# schema.net
KiCad netlist of a schematic drawn in EAGLE
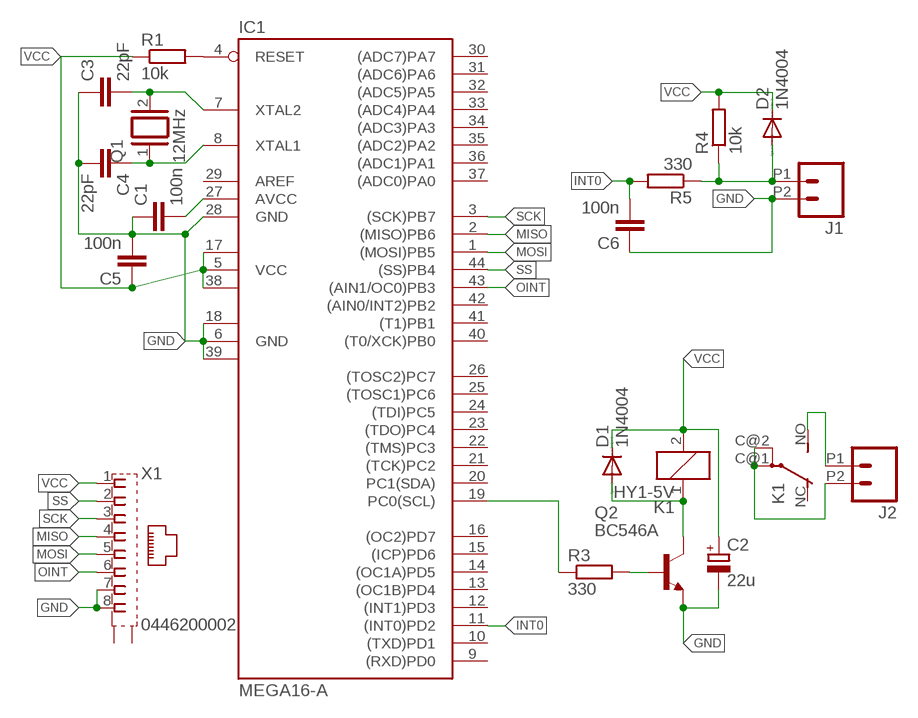
[diagram p0: schematic, sheet 1]

(export (version "E")
  (design (tool "Eeschema 10.0.6"))
  (components
    (comp (ref "C1")
      (value "100n")
      (footprint "eagle-import:C050-024X044")
      (libsource (lib "eagle-import") (part "C-EU050-024X044"))
    )
    (comp (ref "C2")
      (value "22u")
      (footprint "eagle-import:E2,5-6")
      (libsource (lib "eagle-import") (part "CPOL-EUE2.5-6"))
    )
    (comp (ref "C3")
      (value "22pF")
      (footprint "eagle-import:C050-024X044")
      (libsource (lib "eagle-import") (part "C-EU050-024X044"))
    )
    (comp (ref "C4")
      (value "22pF")
      (footprint "eagle-import:C050-024X044")
      (libsource (lib "eagle-import") (part "C-EU050-024X044"))
    )
    (comp (ref "C5")
      (value "100n")
      (footprint "eagle-import:C050-024X044")
      (libsource (lib "eagle-import") (part "C-EU050-024X044"))
    )
    (comp (ref "C6")
      (value "100n")
      (footprint "eagle-import:C050-024X044")
      (libsource (lib "eagle-import") (part "C-EU050-024X044"))
    )
    (comp (ref "D1")
      (value "1N4004")
      (footprint "eagle-import:DO41-10")
      (libsource (lib "eagle-import") (part "1N4004"))
    )
    (comp (ref "D2")
      (value "1N4004")
      (footprint "eagle-import:DO41-10")
      (libsource (lib "eagle-import") (part "1N4004"))
    )
    (comp (ref "IC1")
      (value "MEGA16-A")
      (footprint "eagle-import:TQFP44")
      (fields (field (name "MPN") "ATMEGA16-16AU"))
      (libsource (lib "eagle-import") (part "MEGA16-A"))
    )
    (comp (ref "J1")
      (value "M022.54MM_SCREWTERM")
      (footprint "eagle-import:1X02_2.54_SCREWTERM")
      (libsource (lib "eagle-import") (part "M022.54MM_SCREWTERM"))
    )
    (comp (ref "J2")
      (value "M022.54MM_SCREWTERM")
      (footprint "eagle-import:1X02_2.54_SCREWTERM")
      (libsource (lib "eagle-import") (part "M022.54MM_SCREWTERM"))
    )
    (comp (ref "K1")
      (value "HY1-5V")
      (footprint "eagle-import:HY")
      (fields (field (name "MF") "AROMAT/ MATSUSHITA"))
      (libsource (lib "eagle-import") (part "HY1-5V"))
    )
    (comp (ref "Q1")
      (value "12MHz")
      (footprint "eagle-import:QS")
      (libsource (lib "eagle-import") (part "XTAL/S"))
    )
    (comp (ref "Q2")
      (value "BC546A")
      (footprint "eagle-import:TO92-EBC")
      (libsource (lib "eagle-import") (part "BC546A"))
    )
    (comp (ref "R1")
      (value "10k")
      (footprint "eagle-import:0204_7")
      (libsource (lib "eagle-import") (part "R-EU_0204/7"))
    )
    (comp (ref "R3")
      (value "330")
      (footprint "eagle-import:0204_7")
      (libsource (lib "eagle-import") (part "R-EU_0204/7"))
    )
    (comp (ref "R4")
      (value "10k")
      (footprint "eagle-import:0204_7")
      (libsource (lib "eagle-import") (part "R-EU_0204/7"))
    )
    (comp (ref "R5")
      (value "330")
      (footprint "eagle-import:0204_7")
      (libsource (lib "eagle-import") (part "R-EU_0204/7"))
    )
    (comp (ref "X1")
      (value "0446200002")
      (footprint "eagle-import:0446200002")
      (fields (field (name "MF") "MOLEX"))
      (libsource (lib "eagle-import") (part "0446200002"))
    )
  )
  (nets
    (net (code "1") (name "GND") (class "Default")
      (node (ref "C1") (pin "1") (pinfunction "1_1") (pintype "passive"))
      (node (ref "C2") (pin "-") (pinfunction "-_-") (pintype "passive"))
      (node (ref "C3") (pin "1") (pinfunction "1_1") (pintype "passive"))
      (node (ref "C4") (pin "2") (pinfunction "2_2") (pintype "passive"))
      (node (ref "C5") (pin "2") (pinfunction "2_2") (pintype "passive"))
      (node (ref "C6") (pin "1") (pinfunction "1_1") (pintype "passive"))
      (node (ref "IC1") (pin "18") (pinfunction "GND1_18") (pintype "power_in"))
      (node (ref "IC1") (pin "28") (pinfunction "GND_28") (pintype "power_in"))
      (node (ref "IC1") (pin "39") (pinfunction "GND2_39") (pintype "power_in"))
      (node (ref "IC1") (pin "6") (pinfunction "GND_6") (pintype "power_in"))
      (node (ref "J1") (pin "P2") (pinfunction "2_P2") (pintype "passive"))
      (node (ref "Q2") (pin "E") (pinfunction "E_E") (pintype "passive"))
      (node (ref "X1") (pin "7") (pinfunction "7_7") (pintype "passive"))
      (node (ref "X1") (pin "8") (pinfunction "8_8") (pintype "passive"))
    )
    (net (code "2") (name "INT0") (class "Default")
      (node (ref "C6") (pin "2") (pinfunction "2_2") (pintype "passive"))
      (node (ref "IC1") (pin "11") (pinfunction "(INT0)PD2_11") (pintype "bidirectional"))
      (node (ref "R5") (pin "2") (pinfunction "2_2") (pintype "passive"))
    )
    (net (code "3") (name "MISO") (class "Default")
      (node (ref "IC1") (pin "2") (pinfunction "(MISO)PB6_2") (pintype "bidirectional"))
      (node (ref "X1") (pin "4") (pinfunction "4_4") (pintype "passive"))
    )
    (net (code "4") (name "MOSI") (class "Default")
      (node (ref "IC1") (pin "1") (pinfunction "(MOSI)PB5_1") (pintype "bidirectional"))
      (node (ref "X1") (pin "5") (pinfunction "5_5") (pintype "passive"))
    )
    (net (code "5") (name "Net-(D1-PadA)") (class "Default")
      (node (ref "D1") (pin "A") (pinfunction "A_A") (pintype "passive"))
      (node (ref "K1") (pin "1") (pinfunction "1_1") (pintype "passive"))
      (node (ref "Q2") (pin "C") (pinfunction "C_C") (pintype "passive"))
    )
    (net (code "6") (name "Net-(IC1-AVCC)") (class "Default")
      (node (ref "C1") (pin "2") (pinfunction "2_2") (pintype "passive"))
      (node (ref "IC1") (pin "27") (pinfunction "AVCC_27") (pintype "power_in"))
    )
    (net (code "7") (name "Net-(IC1-PC0(SCL))") (class "Default")
      (node (ref "IC1") (pin "19") (pinfunction "PC0(SCL)_19") (pintype "bidirectional"))
      (node (ref "R3") (pin "1") (pinfunction "1_1") (pintype "passive"))
    )
    (net (code "8") (name "Net-(IC1-RESET)") (class "Default")
      (node (ref "IC1") (pin "4") (pinfunction "RESET_4") (pintype "input"))
      (node (ref "R1") (pin "2") (pinfunction "2_2") (pintype "passive"))
    )
    (net (code "9") (name "Net-(IC1-XTAL1)") (class "Default")
      (node (ref "C4") (pin "1") (pinfunction "1_1") (pintype "passive"))
      (node (ref "IC1") (pin "8") (pinfunction "XTAL1_8") (pintype "bidirectional"))
      (node (ref "Q1") (pin "1") (pinfunction "1_1") (pintype "passive"))
    )
    (net (code "10") (name "Net-(IC1-XTAL2)") (class "Default")
      (node (ref "C3") (pin "2") (pinfunction "2_2") (pintype "passive"))
      (node (ref "IC1") (pin "7") (pinfunction "XTAL2_7") (pintype "bidirectional"))
      (node (ref "Q1") (pin "2") (pinfunction "2_2") (pintype "passive"))
    )
    (net (code "11") (name "Net-(J1-1)") (class "Default")
      (node (ref "D2") (pin "A") (pinfunction "A_A") (pintype "passive"))
      (node (ref "J1") (pin "P1") (pinfunction "1_P1") (pintype "passive"))
      (node (ref "R4") (pin "1") (pinfunction "1_1") (pintype "passive"))
      (node (ref "R5") (pin "1") (pinfunction "1_1") (pintype "passive"))
    )
    (net (code "12") (name "Net-(J2-1)") (class "Default")
      (node (ref "J2") (pin "P1") (pinfunction "1_P1") (pintype "passive"))
      (node (ref "K1") (pin "NO") (pinfunction "S_NO") (pintype "passive"))
    )
    (net (code "13") (name "Net-(J2-2)") (class "Default")
      (node (ref "J2") (pin "P2") (pinfunction "2_P2") (pintype "passive"))
      (node (ref "K1") (pin "C@1") (pinfunction "P_C@1") (pintype "passive"))
      (node (ref "K1") (pin "C@2") (pinfunction "P_C@2") (pintype "passive"))
    )
    (net (code "14") (name "Net-(Q2-PadB)") (class "Default")
      (node (ref "Q2") (pin "B") (pinfunction "B_B") (pintype "passive"))
      (node (ref "R3") (pin "2") (pinfunction "2_2") (pintype "passive"))
    )
    (net (code "15") (name "OINT") (class "Default")
      (node (ref "IC1") (pin "43") (pinfunction "(AIN1/OC0)PB3_43") (pintype "bidirectional"))
      (node (ref "X1") (pin "6") (pinfunction "6_6") (pintype "passive"))
    )
    (net (code "16") (name "SCK") (class "Default")
      (node (ref "IC1") (pin "3") (pinfunction "(SCK)PB7_3") (pintype "bidirectional"))
      (node (ref "X1") (pin "3") (pinfunction "3_3") (pintype "passive"))
    )
    (net (code "17") (name "SS") (class "Default")
      (node (ref "IC1") (pin "44") (pinfunction "(SS)PB4_44") (pintype "bidirectional"))
      (node (ref "X1") (pin "2") (pinfunction "2_2") (pintype "passive"))
    )
    (net (code "18") (name "VCC") (class "Default")
      (node (ref "C2") (pin "+") (pinfunction "+_+") (pintype "passive"))
      (node (ref "C5") (pin "1") (pinfunction "1_1") (pintype "passive"))
      (node (ref "D1") (pin "C") (pinfunction "C_C") (pintype "passive"))
      (node (ref "D2") (pin "C") (pinfunction "C_C") (pintype "passive"))
      (node (ref "IC1") (pin "17") (pinfunction "VCC1_17") (pintype "power_in"))
      (node (ref "IC1") (pin "38") (pinfunction "VCC2_38") (pintype "power_in"))
      (node (ref "IC1") (pin "5") (pinfunction "VCC_5") (pintype "power_in"))
      (node (ref "K1") (pin "2") (pinfunction "2_2") (pintype "passive"))
      (node (ref "R1") (pin "1") (pinfunction "1_1") (pintype "passive"))
      (node (ref "R4") (pin "2") (pinfunction "2_2") (pintype "passive"))
      (node (ref "X1") (pin "1") (pinfunction "1_1") (pintype "passive"))
    )
    (net (code "19") (name "unconnected-(IC1-(ADC0)PA0-Pad37)") (class "Default")
      (node (ref "IC1") (pin "37") (pinfunction "(ADC0)PA0_37") (pintype "bidirectional"))
    )
    (net (code "20") (name "unconnected-(IC1-(ADC1)PA1-Pad36)") (class "Default")
      (node (ref "IC1") (pin "36") (pinfunction "(ADC1)PA1_36") (pintype "bidirectional"))
    )
    (net (code "21") (name "unconnected-(IC1-(ADC2)PA2-Pad35)") (class "Default")
      (node (ref "IC1") (pin "35") (pinfunction "(ADC2)PA2_35") (pintype "bidirectional"))
    )
    (net (code "22") (name "unconnected-(IC1-(ADC3)PA3-Pad34)") (class "Default")
      (node (ref "IC1") (pin "34") (pinfunction "(ADC3)PA3_34") (pintype "bidirectional"))
    )
    (net (code "23") (name "unconnected-(IC1-(ADC4)PA4-Pad33)") (class "Default")
      (node (ref "IC1") (pin "33") (pinfunction "(ADC4)PA4_33") (pintype "bidirectional"))
    )
    (net (code "24") (name "unconnected-(IC1-(ADC5)PA5-Pad32)") (class "Default")
      (node (ref "IC1") (pin "32") (pinfunction "(ADC5)PA5_32") (pintype "bidirectional"))
    )
    (net (code "25") (name "unconnected-(IC1-(ADC6)PA6-Pad31)") (class "Default")
      (node (ref "IC1") (pin "31") (pinfunction "(ADC6)PA6_31") (pintype "bidirectional"))
    )
    (net (code "26") (name "unconnected-(IC1-(ADC7)PA7-Pad30)") (class "Default")
      (node (ref "IC1") (pin "30") (pinfunction "(ADC7)PA7_30") (pintype "bidirectional"))
    )
    (net (code "27") (name "unconnected-(IC1-(AIN0{slash}INT2)PB2-Pad42)") (class "Default")
      (node (ref "IC1") (pin "42") (pinfunction "(AIN0/INT2)PB2_42") (pintype "bidirectional"))
    )
    (net (code "28") (name "unconnected-(IC1-(ICP)PD6-Pad15)") (class "Default")
      (node (ref "IC1") (pin "15") (pinfunction "(ICP)PD6_15") (pintype "bidirectional"))
    )
    (net (code "29") (name "unconnected-(IC1-(INT1)PD3-Pad12)") (class "Default")
      (node (ref "IC1") (pin "12") (pinfunction "(INT1)PD3_12") (pintype "bidirectional"))
    )
    (net (code "30") (name "unconnected-(IC1-(OC1A)PD5-Pad14)") (class "Default")
      (node (ref "IC1") (pin "14") (pinfunction "(OC1A)PD5_14") (pintype "bidirectional"))
    )
    (net (code "31") (name "unconnected-(IC1-(OC1B)PD4-Pad13)") (class "Default")
      (node (ref "IC1") (pin "13") (pinfunction "(OC1B)PD4_13") (pintype "bidirectional"))
    )
    (net (code "32") (name "unconnected-(IC1-(OC2)PD7-Pad16)") (class "Default")
      (node (ref "IC1") (pin "16") (pinfunction "(OC2)PD7_16") (pintype "bidirectional"))
    )
    (net (code "33") (name "unconnected-(IC1-(RXD)PD0-Pad9)") (class "Default")
      (node (ref "IC1") (pin "9") (pinfunction "(RXD)PD0_9") (pintype "bidirectional"))
    )
    (net (code "34") (name "unconnected-(IC1-(T0{slash}XCK)PB0-Pad40)") (class "Default")
      (node (ref "IC1") (pin "40") (pinfunction "(T0/XCK)PB0_40") (pintype "bidirectional"))
    )
    (net (code "35") (name "unconnected-(IC1-(T1)PB1-Pad41)") (class "Default")
      (node (ref "IC1") (pin "41") (pinfunction "(T1)PB1_41") (pintype "bidirectional"))
    )
    (net (code "36") (name "unconnected-(IC1-(TCK)PC2-Pad21)") (class "Default")
      (node (ref "IC1") (pin "21") (pinfunction "(TCK)PC2_21") (pintype "bidirectional"))
    )
    (net (code "37") (name "unconnected-(IC1-(TDI)PC5-Pad24)") (class "Default")
      (node (ref "IC1") (pin "24") (pinfunction "(TDI)PC5_24") (pintype "bidirectional"))
    )
    (net (code "38") (name "unconnected-(IC1-(TDO)PC4-Pad23)") (class "Default")
      (node (ref "IC1") (pin "23") (pinfunction "(TDO)PC4_23") (pintype "bidirectional"))
    )
    (net (code "39") (name "unconnected-(IC1-(TMS)PC3-Pad22)") (class "Default")
      (node (ref "IC1") (pin "22") (pinfunction "(TMS)PC3_22") (pintype "bidirectional"))
    )
    (net (code "40") (name "unconnected-(IC1-(TOSC1)PC6-Pad25)") (class "Default")
      (node (ref "IC1") (pin "25") (pinfunction "(TOSC1)PC6_25") (pintype "bidirectional"))
    )
    (net (code "41") (name "unconnected-(IC1-(TOSC2)PC7-Pad26)") (class "Default")
      (node (ref "IC1") (pin "26") (pinfunction "(TOSC2)PC7_26") (pintype "bidirectional"))
    )
    (net (code "42") (name "unconnected-(IC1-(TXD)PD1-Pad10)") (class "Default")
      (node (ref "IC1") (pin "10") (pinfunction "(TXD)PD1_10") (pintype "bidirectional"))
    )
    (net (code "43") (name "unconnected-(IC1-AREF-Pad29)") (class "Default")
      (node (ref "IC1") (pin "29") (pinfunction "AREF_29") (pintype "passive"))
    )
    (net (code "44") (name "unconnected-(IC1-PC1(SDA)-Pad20)") (class "Default")
      (node (ref "IC1") (pin "20") (pinfunction "PC1(SDA)_20") (pintype "bidirectional"))
    )
    (net (code "45") (name "unconnected-(K1B-O-PadNC)") (class "Default")
      (node (ref "K1") (pin "NC") (pinfunction "O_NC") (pintype "passive"))
    )
    (net (code "46") (name "unconnected-(X1-S1-PadS@1)") (class "Default")
      (node (ref "X1") (pin "S@1") (pinfunction "S1_S@1") (pintype "passive"))
    )
    (net (code "47") (name "unconnected-(X1-S2-PadS@2)") (class "Default")
      (node (ref "X1") (pin "S@2") (pinfunction "S2_S@2") (pintype "passive"))
    )
  )
)
